# switcher1V35.net
KiCad netlist of a schematic drawn in Altium Designer
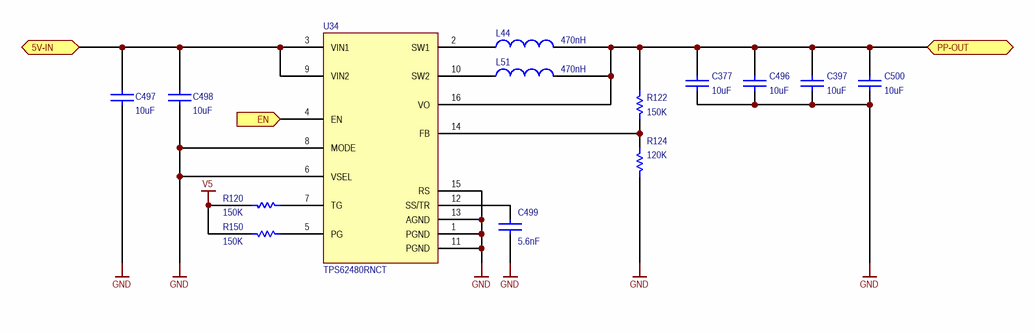
[diagram p0: switcher1V35.SchDoc]

(export (version "E")
  (design (tool "Eeschema 10.0.6"))
  (components
    (comp (ref "C377")
      (value "10uF")
      (footprint "generic:0603")
      (description "Ceramic Capacitor 10uF ±20% 25V X5R 0603")
      (fields (field (name "MANUFACTURER") "Samsung") (field (name "VOLTAGE") "25V"))
      (libsource (lib "generic") (part "CAP 0603"))
    )
    (comp (ref "C397")
      (value "10uF")
      (footprint "generic:0603")
      (description "Ceramic Capacitor 10uF ±20% 25V X5R 0603")
      (fields (field (name "MANUFACTURER") "Samsung") (field (name "VOLTAGE") "25V"))
      (libsource (lib "generic") (part "CAP 0603"))
    )
    (comp (ref "C496")
      (value "10uF")
      (footprint "generic:0603")
      (description "Ceramic Capacitor 10uF ±20% 25V X5R 0603")
      (fields (field (name "MANUFACTURER") "Samsung") (field (name "VOLTAGE") "25V"))
      (libsource (lib "generic") (part "CAP 0603"))
    )
    (comp (ref "C497")
      (value "10uF")
      (footprint "generic:0603")
      (description "Ceramic Capacitor 10uF ±20% 25V X5R 0603")
      (fields (field (name "MANUFACTURER") "Samsung") (field (name "VOLTAGE") "25V"))
      (libsource (lib "generic") (part "CAP 0603"))
    )
    (comp (ref "C498")
      (value "10uF")
      (footprint "generic:0603")
      (description "Ceramic Capacitor 10uF ±20% 25V X5R 0603")
      (fields (field (name "MANUFACTURER") "Samsung") (field (name "VOLTAGE") "25V"))
      (libsource (lib "generic") (part "CAP 0603"))
    )
    (comp (ref "C499")
      (value "5.6nF")
      (footprint "0603")
      (description "Ceramic Capacitor 5.6nF ±5% 50V NP0 0603")
      (fields (field (name "VOLTAGE") "50V") (field (name "MANUFACTURER") "TDK"))
      (libsource (lib "generic") (part "CAP 0402"))
    )
    (comp (ref "C500")
      (value "10uF")
      (footprint "generic:0603")
      (description "Ceramic Capacitor 10uF ±20% 25V X5R 0603")
      (fields (field (name "MANUFACTURER") "Samsung") (field (name "VOLTAGE") "25V"))
      (libsource (lib "generic") (part "CAP 0603"))
    )
    (comp (ref "L44")
      (value "470nH")
      (footprint "DFE2520")
      (description "Shielded Powdered Iron Power Inductor 470nH ±20% 4.9A SMD")
      (fields (field (name "MANUFACTURER") "Murata") (field (name "TOLERANCE") "±20%"))
      (libsource (lib "Miscellaneous Devices") (part "Inductor"))
    )
    (comp (ref "L51")
      (value "470nH")
      (footprint "DFE2520")
      (description "Shielded Powdered Iron Power Inductor 470nH ±20% 4.9A SMD")
      (fields (field (name "MANUFACTURER") "Murata") (field (name "TOLERANCE") "±20%"))
      (libsource (lib "Miscellaneous Devices") (part "Inductor"))
    )
    (comp (ref "R120")
      (value "150K")
      (footprint "generic:0402")
      (description "Thick Film Resistor 150k ±1% 0402")
      (fields (field (name "MANUFACTURER") "Panasonic") (field (name "TOLERANCE") "±1%"))
      (libsource (lib "Graviton") (part "RES 0402"))
    )
    (comp (ref "R122")
      (value "150K")
      (footprint "generic:0402")
      (description "Thick Film Resistor 150k ±1% 0402")
      (fields (field (name "MANUFACTURER") "Panasonic") (field (name "TOLERANCE") "±1%"))
      (libsource (lib "Graviton") (part "RES 0402"))
    )
    (comp (ref "R124")
      (value "120K")
      (footprint "generic:0402")
      (description "Thick Film Resistor 120k ±1% 0402")
      (fields (field (name "MANUFACTURER") "Panasonic") (field (name "TOLERANCE") "±1%"))
      (libsource (lib "Graviton") (part "RES 0402"))
    )
    (comp (ref "R150")
      (value "150K")
      (footprint "generic:0402")
      (description "Thick Film Resistor 150k ±1% 0402")
      (fields (field (name "MANUFACTURER") "Panasonic") (field (name "TOLERANCE") "±1%"))
      (libsource (lib "Graviton") (part "RES 0402"))
    )
    (comp (ref "U34")
      (value "TPS62480RNCT")
      (footprint "RNC-VQFN-16")
      (description "6A Dual Phase Ultra-Compact Buck Supply")
      (fields (field (name "MANUFACTURER") "Texas Instruments"))
      (libsource (lib "ti") (part "TPS62480"))
    )
  )
  (nets
    (net (code "1") (name "/5V-IN") (class "Default")
      (node (ref "C497") (pin "2") (pinfunction "2_2") (pintype "passive"))
      (node (ref "C498") (pin "2") (pinfunction "2_2") (pintype "passive"))
      (node (ref "U34") (pin "3") (pinfunction "VIN1_3") (pintype "passive"))
      (node (ref "U34") (pin "9") (pinfunction "VIN2_9") (pintype "passive"))
    )
    (net (code "2") (name "/EN") (class "Default")
      (node (ref "U34") (pin "4") (pinfunction "EN_4") (pintype "passive"))
    )
    (net (code "3") (name "/PP-OUT") (class "Default")
      (node (ref "C377") (pin "2") (pinfunction "2_2") (pintype "passive"))
      (node (ref "C397") (pin "2") (pinfunction "2_2") (pintype "passive"))
      (node (ref "C496") (pin "2") (pinfunction "2_2") (pintype "passive"))
      (node (ref "C500") (pin "2") (pinfunction "2_2") (pintype "passive"))
      (node (ref "L44") (pin "2") (pinfunction "2_2") (pintype "passive"))
      (node (ref "L51") (pin "2") (pinfunction "2_2") (pintype "passive"))
      (node (ref "R122") (pin "1") (pinfunction "1_1") (pintype "passive"))
      (node (ref "U34") (pin "16") (pinfunction "VO_16") (pintype "passive"))
    )
    (net (code "4") (name "GND") (class "Default")
      (node (ref "C377") (pin "1") (pinfunction "1_1") (pintype "passive"))
      (node (ref "C397") (pin "1") (pinfunction "1_1") (pintype "passive"))
      (node (ref "C496") (pin "1") (pinfunction "1_1") (pintype "passive"))
      (node (ref "C497") (pin "1") (pinfunction "1_1") (pintype "passive"))
      (node (ref "C498") (pin "1") (pinfunction "1_1") (pintype "passive"))
      (node (ref "C499") (pin "1") (pinfunction "1_1") (pintype "passive"))
      (node (ref "C500") (pin "1") (pinfunction "1_1") (pintype "passive"))
      (node (ref "R124") (pin "2") (pinfunction "2_2") (pintype "passive"))
      (node (ref "U34") (pin "1") (pinfunction "PGND_1") (pintype "passive"))
      (node (ref "U34") (pin "11") (pinfunction "PGND_11") (pintype "passive"))
      (node (ref "U34") (pin "13") (pinfunction "AGND_13") (pintype "passive"))
      (node (ref "U34") (pin "15") (pinfunction "RS_15") (pintype "passive"))
      (node (ref "U34") (pin "6") (pinfunction "VSEL_6") (pintype "passive"))
      (node (ref "U34") (pin "8") (pinfunction "MODE_8") (pintype "passive"))
    )
    (net (code "5") (name "Net-(U34-FB)") (class "Default")
      (node (ref "R122") (pin "2") (pinfunction "2_2") (pintype "passive"))
      (node (ref "R124") (pin "1") (pinfunction "1_1") (pintype "passive"))
      (node (ref "U34") (pin "14") (pinfunction "FB_14") (pintype "passive"))
    )
    (net (code "6") (name "Net-(U34-PG)") (class "Default")
      (node (ref "R150") (pin "2") (pinfunction "2_2") (pintype "passive"))
      (node (ref "U34") (pin "5") (pinfunction "PG_5") (pintype "passive"))
    )
    (net (code "7") (name "Net-(U34-SS{slash}TR)") (class "Default")
      (node (ref "C499") (pin "2") (pinfunction "2_2") (pintype "passive"))
      (node (ref "U34") (pin "12") (pinfunction "SS/TR_12") (pintype "passive"))
    )
    (net (code "8") (name "Net-(U34-SW1)") (class "Default")
      (node (ref "L44") (pin "1") (pinfunction "1_1") (pintype "passive"))
      (node (ref "U34") (pin "2") (pinfunction "SW1_2") (pintype "passive"))
    )
    (net (code "9") (name "Net-(U34-SW2)") (class "Default")
      (node (ref "L51") (pin "1") (pinfunction "1_1") (pintype "passive"))
      (node (ref "U34") (pin "10") (pinfunction "SW2_10") (pintype "passive"))
    )
    (net (code "10") (name "Net-(U34-TG)") (class "Default")
      (node (ref "R120") (pin "2") (pinfunction "2_2") (pintype "passive"))
      (node (ref "U34") (pin "7") (pinfunction "TG_7") (pintype "passive"))
    )
    (net (code "11") (name "V5") (class "Default")
      (node (ref "R120") (pin "1") (pinfunction "1_1") (pintype "passive"))
      (node (ref "R150") (pin "1") (pinfunction "1_1") (pintype "passive"))
    )
  )
)
